# communication_module_20190916_bus-revise.net
KiCad netlist of a schematic drawn in EAGLE
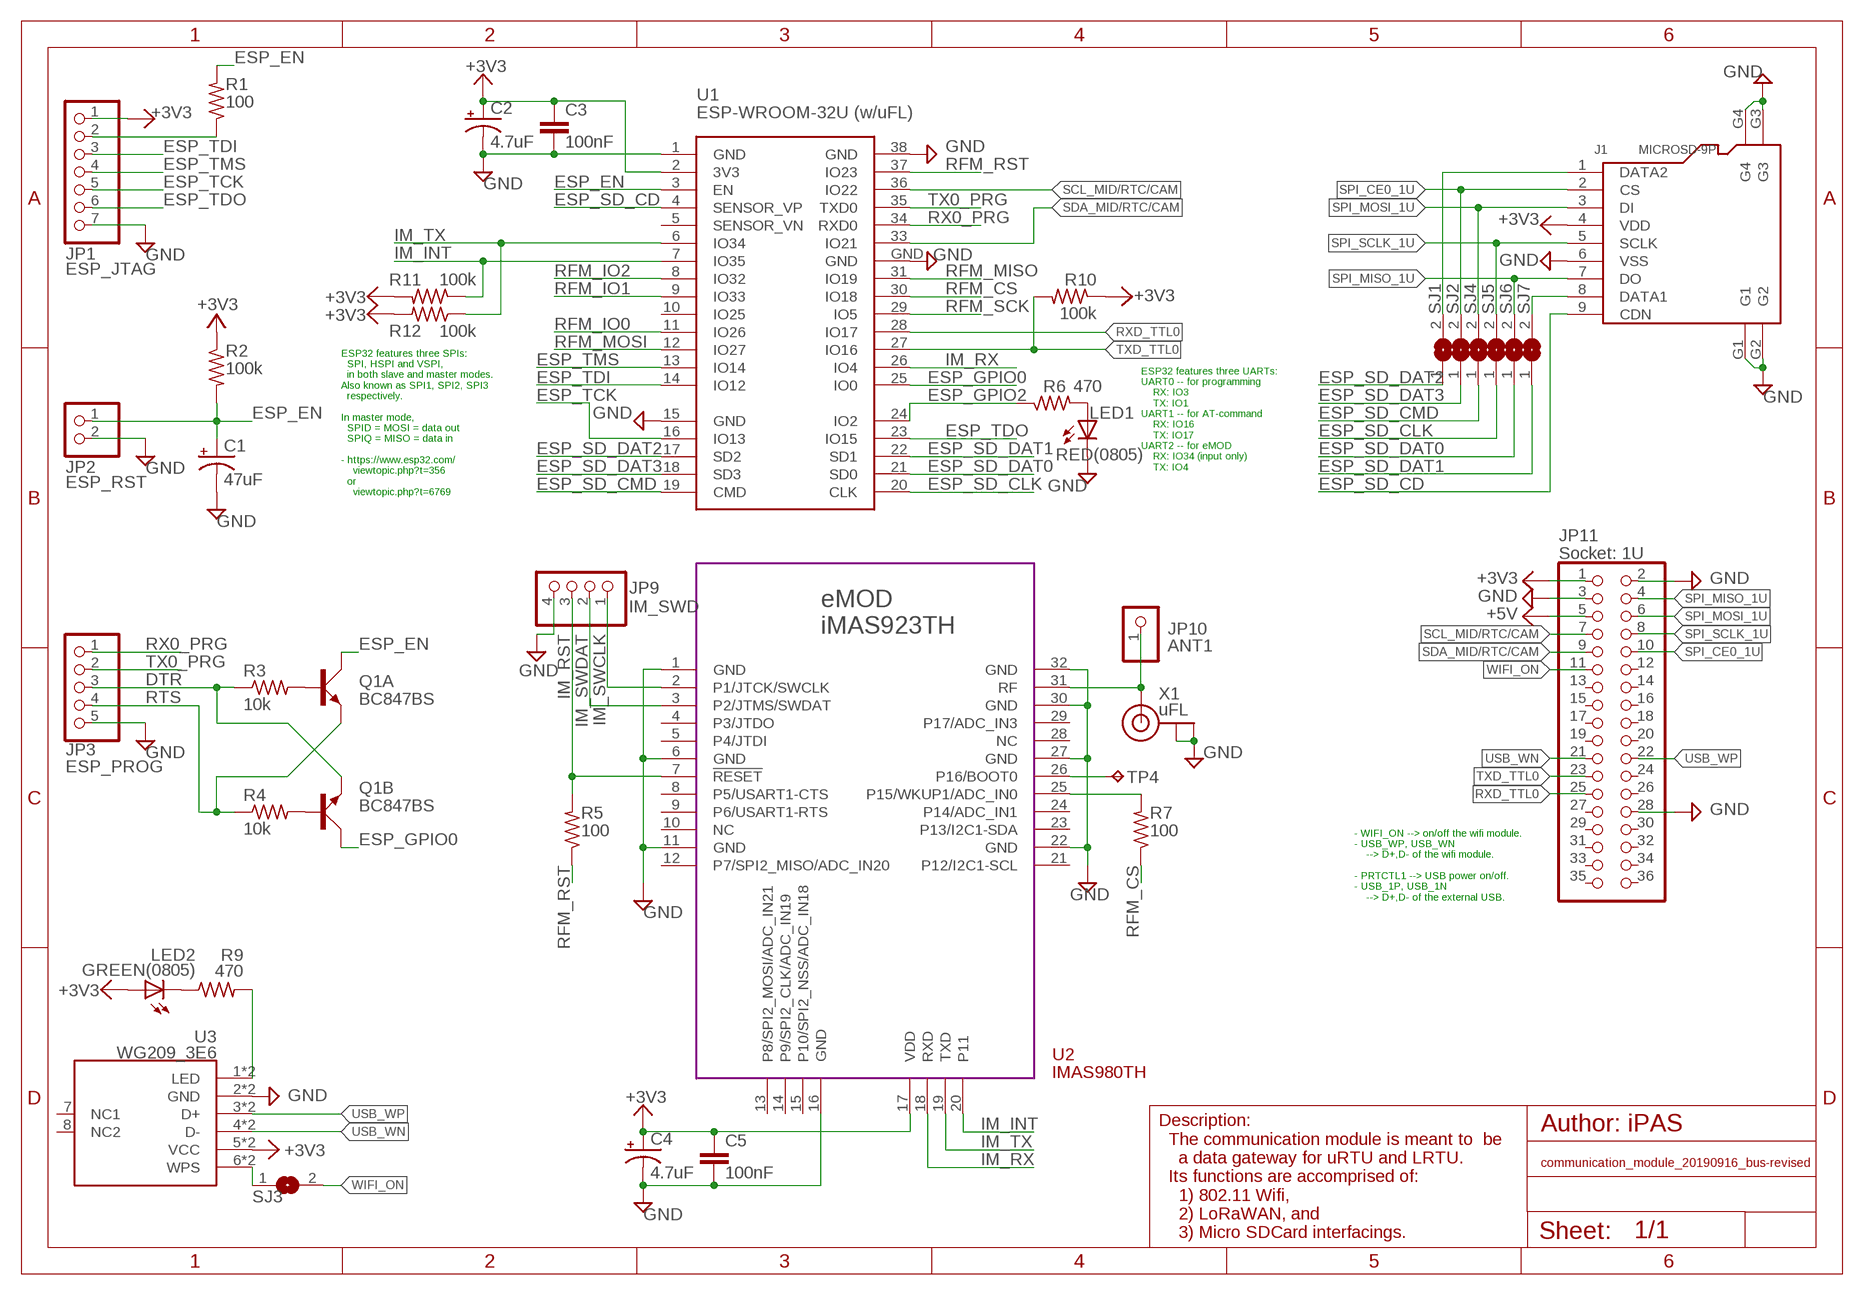
[diagram p0: schematic, sheet 1]

(export (version "E")
  (design (tool "Eeschema 10.0.6"))
  (components
    (comp (ref "C1")
      (value "47uF")
      (footprint "eagle-import:RCL_150CLZ-1014")
      (libsource (lib "eagle-import") (part "RCL_CPOL-US150CLZ-1014"))
    )
    (comp (ref "C2")
      (value "4.7uF")
      (footprint "eagle-import:RCL_150CLZ-1014")
      (libsource (lib "eagle-import") (part "RCL_CPOL-US150CLZ-1014"))
    )
    (comp (ref "C3")
      (value "100nF")
      (footprint "eagle-import:RCL_C1206")
      (libsource (lib "eagle-import") (part "RCL_C-EUC1206"))
    )
    (comp (ref "C4")
      (value "4.7uF")
      (footprint "eagle-import:RCL_150CLZ-1014")
      (libsource (lib "eagle-import") (part "RCL_CPOL-US150CLZ-1014"))
    )
    (comp (ref "C5")
      (value "100nF")
      (footprint "eagle-import:RCL_C1206")
      (libsource (lib "eagle-import") (part "RCL_C-EUC1206"))
    )
    (comp (ref "J1")
      (value "MICROSD-9P")
      (footprint "eagle-import:MICRO-SD9+4P-SMD-16.1X14.5X1.85MM")
      (libsource (lib "eagle-import") (part "MICRO-SD-CARD-HOLDER-9P"))
    )
    (comp (ref "JP1")
      (value "ESP_JTAG")
      (footprint "eagle-import:1X07")
      (libsource (lib "eagle-import") (part "PINHD-1X7"))
    )
    (comp (ref "JP2")
      (value "ESP_RST")
      (footprint "eagle-import:1X02")
      (libsource (lib "eagle-import") (part "PINHD-1X2"))
    )
    (comp (ref "JP3")
      (value "ESP_PROG")
      (footprint "eagle-import:1X05")
      (libsource (lib "eagle-import") (part "PINHD-1X5"))
    )
    (comp (ref "JP9")
      (value "IM_SWD")
      (footprint "eagle-import:1X04")
      (libsource (lib "eagle-import") (part "PINHD-1X4"))
    )
    (comp (ref "JP10")
      (value "ANT1")
      (footprint "eagle-import:1X01_ROUND")
      (libsource (lib "eagle-import") (part "HEADER-1X1ROUND"))
    )
    (comp (ref "JP11")
      (value "Socket: 1U")
      (footprint "eagle-import:2X18")
      (libsource (lib "eagle-import") (part "PINHD-2X18"))
    )
    (comp (ref "LED1")
      (value "RED(0805)")
      (footprint "eagle-import:CHIP-LED0805")
      (libsource (lib "eagle-import") (part "LEDCHIP-LED0805"))
    )
    (comp (ref "LED2")
      (value "GREEN(0805)")
      (footprint "eagle-import:CHIP-LED0805")
      (libsource (lib "eagle-import") (part "LEDCHIP-LED0805"))
    )
    (comp (ref "Q1")
      (value "BC847BS")
      (footprint "eagle-import:SOT363_PHILIPS")
      (libsource (lib "eagle-import") (part "BC847BS"))
    )
    (comp (ref "R1")
      (value "100")
      (footprint "eagle-import:RCL_M0805")
      (libsource (lib "eagle-import") (part "RCL_R-USM0805"))
    )
    (comp (ref "R2")
      (value "100k")
      (footprint "eagle-import:RCL_M0805")
      (libsource (lib "eagle-import") (part "RCL_R-USM0805"))
    )
    (comp (ref "R3")
      (value "10k")
      (footprint "eagle-import:RCL_M0805")
      (libsource (lib "eagle-import") (part "RCL_R-USM0805"))
    )
    (comp (ref "R4")
      (value "10k")
      (footprint "eagle-import:RCL_M0805")
      (libsource (lib "eagle-import") (part "RCL_R-USM0805"))
    )
    (comp (ref "R5")
      (value "100")
      (footprint "eagle-import:RCL_M0805")
      (libsource (lib "eagle-import") (part "RCL_R-USM0805"))
    )
    (comp (ref "R6")
      (value "470")
      (footprint "eagle-import:RCL_M0805")
      (libsource (lib "eagle-import") (part "RCL_R-USM0805"))
    )
    (comp (ref "R7")
      (value "100")
      (footprint "eagle-import:RCL_M0805")
      (libsource (lib "eagle-import") (part "RCL_R-USM0805"))
    )
    (comp (ref "R9")
      (value "470")
      (footprint "eagle-import:RCL_M0805")
      (libsource (lib "eagle-import") (part "RCL_R-USM0805"))
    )
    (comp (ref "R10")
      (value "100k")
      (footprint "eagle-import:RCL_M0805")
      (libsource (lib "eagle-import") (part "RCL_R-USM0805"))
    )
    (comp (ref "R11")
      (value "100k")
      (footprint "eagle-import:RCL_M0805")
      (libsource (lib "eagle-import") (part "RCL_R-USM0805"))
    )
    (comp (ref "R12")
      (value "100k")
      (footprint "eagle-import:RCL_M0805")
      (libsource (lib "eagle-import") (part "RCL_R-USM0805"))
    )
    (comp (ref "SJ1")
      (value "SOLDERJUMPERREFLOW")
      (footprint "eagle-import:SOLDERJUMPER_REFLOW")
      (libsource (lib "eagle-import") (part "SOLDERJUMPERREFLOW"))
    )
    (comp (ref "SJ2")
      (value "SOLDERJUMPERREFLOW")
      (footprint "eagle-import:SOLDERJUMPER_REFLOW")
      (libsource (lib "eagle-import") (part "SOLDERJUMPERREFLOW"))
    )
    (comp (ref "SJ3")
      (value "SOLDERJUMPERREFLOW")
      (footprint "eagle-import:SOLDERJUMPER_REFLOW")
      (libsource (lib "eagle-import") (part "SOLDERJUMPERREFLOW"))
    )
    (comp (ref "SJ4")
      (value "SOLDERJUMPERREFLOW")
      (footprint "eagle-import:SOLDERJUMPER_REFLOW")
      (libsource (lib "eagle-import") (part "SOLDERJUMPERREFLOW"))
    )
    (comp (ref "SJ5")
      (value "SOLDERJUMPERREFLOW")
      (footprint "eagle-import:SOLDERJUMPER_REFLOW")
      (libsource (lib "eagle-import") (part "SOLDERJUMPERREFLOW"))
    )
    (comp (ref "SJ6")
      (value "SOLDERJUMPERREFLOW")
      (footprint "eagle-import:SOLDERJUMPER_REFLOW")
      (libsource (lib "eagle-import") (part "SOLDERJUMPERREFLOW"))
    )
    (comp (ref "SJ7")
      (value "SOLDERJUMPERREFLOW")
      (footprint "eagle-import:SOLDERJUMPER_REFLOW")
      (libsource (lib "eagle-import") (part "SOLDERJUMPERREFLOW"))
    )
    (comp (ref "TP4")
      (value "TPB1,27")
      (footprint "eagle-import:B1,27")
      (libsource (lib "eagle-import") (part "TPB1,27"))
    )
    (comp (ref "U1")
      (value "ESP-WROOM-32U (w/uFL)")
      (footprint "eagle-import:ESP-WROOM-32")
      (libsource (lib "eagle-import") (part "ESP-WROOM-32"))
    )
    (comp (ref "U2")
      (value "IMAS980TH")
      (footprint "eagle-import:IMAS923TH")
      (libsource (lib "eagle-import") (part "IMAS980TH"))
    )
    (comp (ref "U3")
      (value "WG209_3E6")
      (footprint "eagle-import:WG209")
      (libsource (lib "eagle-import") (part "WG209"))
    )
    (comp (ref "X1")
      (value "uFL")
      (footprint "eagle-import:U.FL")
      (libsource (lib "eagle-import") (part "ANTENNA_U.FL"))
    )
  )
  (nets
    (net (code "1") (name "+3V3") (class "Default")
      (node (ref "C2") (pin "+") (pinfunction "+_+") (pintype "passive"))
      (node (ref "C3") (pin "1") (pinfunction "1_1") (pintype "passive"))
      (node (ref "C4") (pin "+") (pinfunction "+_+") (pintype "passive"))
      (node (ref "C5") (pin "1") (pinfunction "1_1") (pintype "passive"))
      (node (ref "J1") (pin "4") (pinfunction "VDD_4") (pintype "bidirectional"))
      (node (ref "JP1") (pin "1") (pinfunction "1_1") (pintype "passive"))
      (node (ref "JP11") (pin "1") (pinfunction "1_1") (pintype "passive"))
      (node (ref "LED2") (pin "A") (pinfunction "A_A") (pintype "passive"))
      (node (ref "R10") (pin "1") (pinfunction "1_1") (pintype "passive"))
      (node (ref "R11") (pin "2") (pinfunction "2_2") (pintype "passive"))
      (node (ref "R12") (pin "2") (pinfunction "2_2") (pintype "passive"))
      (node (ref "R2") (pin "1") (pinfunction "1_1") (pintype "passive"))
      (node (ref "U1") (pin "2") (pinfunction "3V3_2") (pintype "power_in"))
      (node (ref "U2") (pin "17") (pinfunction "VDD_17") (pintype "power_in"))
      (node (ref "U3") (pin "5") (pinfunction "VCC_5") (pintype "power_in"))
      (node (ref "U3") (pin "5P") (pinfunction "VCC_5P") (pintype "power_in"))
    )
    (net (code "2") (name "+5V") (class "Default")
      (node (ref "JP11") (pin "5") (pinfunction "5_5") (pintype "passive"))
    )
    (net (code "3") (name "/DTR") (class "Default")
      (node (ref "JP3") (pin "3") (pinfunction "3_3") (pintype "passive"))
      (node (ref "Q1") (pin "4") (pinfunction "E_4") (pintype "passive"))
      (node (ref "R3") (pin "1") (pinfunction "1_1") (pintype "passive"))
    )
    (net (code "4") (name "/ESP_EN") (class "Default")
      (node (ref "C1") (pin "+") (pinfunction "+_+") (pintype "passive"))
      (node (ref "JP2") (pin "1") (pinfunction "1_1") (pintype "passive"))
      (node (ref "Q1") (pin "6") (pinfunction "C_6") (pintype "passive"))
      (node (ref "R1") (pin "2") (pinfunction "2_2") (pintype "passive"))
      (node (ref "R2") (pin "2") (pinfunction "2_2") (pintype "passive"))
      (node (ref "U1") (pin "3") (pinfunction "EN_3") (pintype "input"))
    )
    (net (code "5") (name "/ESP_GPIO0") (class "Default")
      (node (ref "Q1") (pin "3") (pinfunction "C_3") (pintype "passive"))
      (node (ref "U1") (pin "25") (pinfunction "IO0_25") (pintype "bidirectional"))
    )
    (net (code "6") (name "/ESP_GPIO2") (class "Default")
      (node (ref "R6") (pin "1") (pinfunction "1_1") (pintype "passive"))
      (node (ref "U1") (pin "24") (pinfunction "IO2_24") (pintype "bidirectional"))
    )
    (net (code "7") (name "/ESP_SD_CD") (class "Default")
      (node (ref "J1") (pin "9") (pinfunction "CDN_9") (pintype "bidirectional"))
      (node (ref "U1") (pin "4") (pinfunction "SENSOR_VP_4") (pintype "bidirectional"))
    )
    (net (code "8") (name "/ESP_SD_CLK") (class "Default")
      (node (ref "SJ5") (pin "1") (pinfunction "1_1") (pintype "passive"))
      (node (ref "U1") (pin "20") (pinfunction "CLK_20") (pintype "bidirectional"))
    )
    (net (code "9") (name "/ESP_SD_CMD") (class "Default")
      (node (ref "SJ4") (pin "1") (pinfunction "1_1") (pintype "passive"))
      (node (ref "U1") (pin "19") (pinfunction "CMD_19") (pintype "bidirectional"))
    )
    (net (code "10") (name "/ESP_SD_DAT0") (class "Default")
      (node (ref "SJ6") (pin "1") (pinfunction "1_1") (pintype "passive"))
      (node (ref "U1") (pin "21") (pinfunction "SD0_21") (pintype "bidirectional"))
    )
    (net (code "11") (name "/ESP_SD_DAT1") (class "Default")
      (node (ref "SJ7") (pin "1") (pinfunction "1_1") (pintype "passive"))
      (node (ref "U1") (pin "22") (pinfunction "SD1_22") (pintype "bidirectional"))
    )
    (net (code "12") (name "/ESP_SD_DAT2") (class "Default")
      (node (ref "SJ1") (pin "1") (pinfunction "1_1") (pintype "passive"))
      (node (ref "U1") (pin "17") (pinfunction "SD2_17") (pintype "bidirectional"))
    )
    (net (code "13") (name "/ESP_SD_DAT3") (class "Default")
      (node (ref "SJ2") (pin "1") (pinfunction "1_1") (pintype "passive"))
      (node (ref "U1") (pin "18") (pinfunction "SD3_18") (pintype "bidirectional"))
    )
    (net (code "14") (name "/ESP_TCK") (class "Default")
      (node (ref "JP1") (pin "5") (pinfunction "5_5") (pintype "passive"))
      (node (ref "U1") (pin "16") (pinfunction "IO13_16") (pintype "bidirectional"))
    )
    (net (code "15") (name "/ESP_TDI") (class "Default")
      (node (ref "JP1") (pin "3") (pinfunction "3_3") (pintype "passive"))
      (node (ref "U1") (pin "14") (pinfunction "IO12_14") (pintype "bidirectional"))
    )
    (net (code "16") (name "/ESP_TDO") (class "Default")
      (node (ref "JP1") (pin "6") (pinfunction "6_6") (pintype "passive"))
      (node (ref "U1") (pin "23") (pinfunction "IO15_23") (pintype "bidirectional"))
    )
    (net (code "17") (name "/ESP_TMS") (class "Default")
      (node (ref "JP1") (pin "4") (pinfunction "4_4") (pintype "passive"))
      (node (ref "U1") (pin "13") (pinfunction "IO14_13") (pintype "bidirectional"))
    )
    (net (code "18") (name "/IM_INT") (class "Default")
      (node (ref "R11") (pin "1") (pinfunction "1_1") (pintype "passive"))
      (node (ref "U1") (pin "7") (pinfunction "IO35_7") (pintype "bidirectional"))
      (node (ref "U2") (pin "20") (pinfunction "P11_20") (pintype "bidirectional"))
    )
    (net (code "19") (name "/IM_RST") (class "Default")
      (node (ref "JP9") (pin "3") (pinfunction "3_3") (pintype "passive"))
      (node (ref "R5") (pin "2") (pinfunction "2_2") (pintype "passive"))
      (node (ref "U2") (pin "7") (pinfunction "~{RESET}_7") (pintype "passive"))
    )
    (net (code "20") (name "/IM_RX") (class "Default")
      (node (ref "U1") (pin "26") (pinfunction "IO4_26") (pintype "bidirectional"))
      (node (ref "U2") (pin "18") (pinfunction "RXD_18") (pintype "bidirectional"))
    )
    (net (code "21") (name "/IM_SWCLK") (class "Default")
      (node (ref "JP9") (pin "1") (pinfunction "1_1") (pintype "passive"))
      (node (ref "U2") (pin "2") (pinfunction "P1/JTCK/SWCLK_2") (pintype "bidirectional"))
    )
    (net (code "22") (name "/IM_SWDAT") (class "Default")
      (node (ref "JP9") (pin "2") (pinfunction "2_2") (pintype "passive"))
      (node (ref "U2") (pin "3") (pinfunction "P2/JTMS/SWDAT_3") (pintype "bidirectional"))
    )
    (net (code "23") (name "/IM_TX") (class "Default")
      (node (ref "R12") (pin "1") (pinfunction "1_1") (pintype "passive"))
      (node (ref "U1") (pin "6") (pinfunction "IO34_6") (pintype "bidirectional"))
      (node (ref "U2") (pin "19") (pinfunction "TXD_19") (pintype "bidirectional"))
    )
    (net (code "24") (name "/RFM_CS") (class "Default")
      (node (ref "R7") (pin "1") (pinfunction "1_1") (pintype "passive"))
      (node (ref "U1") (pin "30") (pinfunction "IO18_30") (pintype "bidirectional"))
    )
    (net (code "25") (name "/RFM_IO0") (class "Default")
      (node (ref "U1") (pin "11") (pinfunction "IO26_11") (pintype "bidirectional"))
    )
    (net (code "26") (name "/RFM_IO1") (class "Default")
      (node (ref "U1") (pin "9") (pinfunction "IO33_9") (pintype "bidirectional"))
    )
    (net (code "27") (name "/RFM_IO2") (class "Default")
      (node (ref "U1") (pin "8") (pinfunction "IO32_8") (pintype "bidirectional"))
    )
    (net (code "28") (name "/RFM_MISO") (class "Default")
      (node (ref "U1") (pin "31") (pinfunction "IO19_31") (pintype "bidirectional"))
    )
    (net (code "29") (name "/RFM_MOSI") (class "Default")
      (node (ref "U1") (pin "12") (pinfunction "IO27_12") (pintype "bidirectional"))
    )
    (net (code "30") (name "/RFM_RST") (class "Default")
      (node (ref "R5") (pin "1") (pinfunction "1_1") (pintype "passive"))
      (node (ref "U1") (pin "37") (pinfunction "IO23_37") (pintype "bidirectional"))
    )
    (net (code "31") (name "/RFM_SCK") (class "Default")
      (node (ref "U1") (pin "29") (pinfunction "IO5_29") (pintype "bidirectional"))
    )
    (net (code "32") (name "/RTS") (class "Default")
      (node (ref "JP3") (pin "4") (pinfunction "4_4") (pintype "passive"))
      (node (ref "Q1") (pin "1") (pinfunction "E_1") (pintype "passive"))
      (node (ref "R4") (pin "1") (pinfunction "1_1") (pintype "passive"))
    )
    (net (code "33") (name "/RX0_PRG") (class "Default")
      (node (ref "JP3") (pin "1") (pinfunction "1_1") (pintype "passive"))
      (node (ref "U1") (pin "34") (pinfunction "RXD0_34") (pintype "bidirectional"))
    )
    (net (code "34") (name "/TX0_PRG") (class "Default")
      (node (ref "JP3") (pin "2") (pinfunction "2_2") (pintype "passive"))
      (node (ref "U1") (pin "35") (pinfunction "TXD0_35") (pintype "bidirectional"))
    )
    (net (code "35") (name "GND") (class "Default")
      (node (ref "C1") (pin "-") (pinfunction "-_-") (pintype "passive"))
      (node (ref "C2") (pin "-") (pinfunction "-_-") (pintype "passive"))
      (node (ref "C3") (pin "2") (pinfunction "2_2") (pintype "passive"))
      (node (ref "C4") (pin "-") (pinfunction "-_-") (pintype "passive"))
      (node (ref "C5") (pin "2") (pinfunction "2_2") (pintype "passive"))
      (node (ref "J1") (pin "6") (pinfunction "VSS_6") (pintype "bidirectional"))
      (node (ref "J1") (pin "G1") (pinfunction "G1_G1") (pintype "bidirectional"))
      (node (ref "J1") (pin "G2") (pinfunction "G2_G2") (pintype "bidirectional"))
      (node (ref "J1") (pin "G3") (pinfunction "G3_G3") (pintype "bidirectional"))
      (node (ref "J1") (pin "G4") (pinfunction "G4_G4") (pintype "bidirectional"))
      (node (ref "JP1") (pin "7") (pinfunction "7_7") (pintype "passive"))
      (node (ref "JP11") (pin "2") (pinfunction "2_2") (pintype "passive"))
      (node (ref "JP11") (pin "28") (pinfunction "28_28") (pintype "passive"))
      (node (ref "JP11") (pin "3") (pinfunction "3_3") (pintype "passive"))
      (node (ref "JP2") (pin "2") (pinfunction "2_2") (pintype "passive"))
      (node (ref "JP3") (pin "5") (pinfunction "5_5") (pintype "passive"))
      (node (ref "JP9") (pin "4") (pinfunction "4_4") (pintype "passive"))
      (node (ref "LED1") (pin "C") (pinfunction "C_C") (pintype "passive"))
      (node (ref "U1") (pin "1") (pinfunction "GND_1") (pintype "power_in"))
      (node (ref "U1") (pin "15") (pinfunction "GND_15") (pintype "power_in"))
      (node (ref "U1") (pin "38") (pinfunction "GND_38") (pintype "power_in"))
      (node (ref "U1") (pin "GND") (pinfunction "GND_GND") (pintype "power_in"))
      (node (ref "U2") (pin "1") (pinfunction "GND_1") (pintype "power_in"))
      (node (ref "U2") (pin "11") (pinfunction "GND_11") (pintype "power_in"))
      (node (ref "U2") (pin "16") (pinfunction "GND_16") (pintype "power_in"))
      (node (ref "U2") (pin "22") (pinfunction "GND_22") (pintype "power_in"))
      (node (ref "U2") (pin "27") (pinfunction "GND_27") (pintype "power_in"))
      (node (ref "U2") (pin "30") (pinfunction "GND_30") (pintype "power_in"))
      (node (ref "U2") (pin "32") (pinfunction "GND_32") (pintype "power_in"))
      (node (ref "U2") (pin "6") (pinfunction "GND_6") (pintype "power_in"))
      (node (ref "U3") (pin "2") (pinfunction "GND_2") (pintype "power_in"))
      (node (ref "U3") (pin "2P") (pinfunction "GND_2P") (pintype "power_in"))
      (node (ref "X1") (pin "1") (pinfunction "GND_1") (pintype "passive"))
      (node (ref "X1") (pin "2") (pinfunction "GND_2") (pintype "passive"))
    )
    (net (code "36") (name "Net-(J1-DATA1)") (class "Default")
      (node (ref "J1") (pin "8") (pinfunction "DATA1_8") (pintype "bidirectional"))
      (node (ref "SJ7") (pin "2") (pinfunction "2_2") (pintype "passive"))
    )
    (net (code "37") (name "Net-(J1-DATA2)") (class "Default")
      (node (ref "J1") (pin "1") (pinfunction "DATA2_1") (pintype "bidirectional"))
      (node (ref "SJ1") (pin "2") (pinfunction "2_2") (pintype "passive"))
    )
    (net (code "38") (name "Net-(JP1-Pad2)") (class "Default")
      (node (ref "JP1") (pin "2") (pinfunction "2_2") (pintype "passive"))
      (node (ref "R1") (pin "1") (pinfunction "1_1") (pintype "passive"))
    )
    (net (code "39") (name "Net-(LED1-PadA)") (class "Default")
      (node (ref "LED1") (pin "A") (pinfunction "A_A") (pintype "passive"))
      (node (ref "R6") (pin "2") (pinfunction "2_2") (pintype "passive"))
    )
    (net (code "40") (name "Net-(LED2-PadC)") (class "Default")
      (node (ref "LED2") (pin "C") (pinfunction "C_C") (pintype "passive"))
      (node (ref "R9") (pin "1") (pinfunction "1_1") (pintype "passive"))
    )
    (net (code "41") (name "Net-(Q1A-B)") (class "Default")
      (node (ref "Q1") (pin "2") (pinfunction "B_2") (pintype "passive"))
      (node (ref "R3") (pin "2") (pinfunction "2_2") (pintype "passive"))
    )
    (net (code "42") (name "Net-(Q1B-B)") (class "Default")
      (node (ref "Q1") (pin "5") (pinfunction "B_5") (pintype "passive"))
      (node (ref "R4") (pin "2") (pinfunction "2_2") (pintype "passive"))
    )
    (net (code "43") (name "Net-(R9-Pad2)") (class "Default")
      (node (ref "R9") (pin "2") (pinfunction "2_2") (pintype "passive"))
      (node (ref "U3") (pin "1") (pinfunction "LED_1") (pintype "bidirectional"))
      (node (ref "U3") (pin "1P") (pinfunction "LED_1P") (pintype "bidirectional"))
    )
    (net (code "44") (name "Net-(SJ3-Pad1)") (class "Default")
      (node (ref "SJ3") (pin "1") (pinfunction "1_1") (pintype "passive"))
      (node (ref "U3") (pin "6") (pinfunction "WPS_6") (pintype "bidirectional"))
      (node (ref "U3") (pin "6P") (pinfunction "WPS_6P") (pintype "bidirectional"))
    )
    (net (code "45") (name "Net-(U2-P15{slash}WKUP1{slash}ADC_IN0)") (class "Default")
      (node (ref "R7") (pin "2") (pinfunction "2_2") (pintype "passive"))
      (node (ref "U2") (pin "25") (pinfunction "P15/WKUP1/ADC_IN0_25") (pintype "bidirectional"))
    )
    (net (code "46") (name "Net-(U2-P16{slash}BOOT0)") (class "Default")
      (node (ref "TP4") (pin "TP") (pinfunction "TP_TP") (pintype "input"))
      (node (ref "U2") (pin "26") (pinfunction "P16/BOOT0_26") (pintype "passive"))
    )
    (net (code "47") (name "Net-(U2-RF)") (class "Default")
      (node (ref "JP10") (pin "1") (pinfunction "1_1") (pintype "passive"))
      (node (ref "U2") (pin "31") (pinfunction "RF_31") (pintype "bidirectional"))
      (node (ref "X1") (pin "3") (pinfunction "SIGNAL_3") (pintype "passive"))
    )
    (net (code "48") (name "RXD_TTL0") (class "Default")
      (node (ref "JP11") (pin "25") (pinfunction "25_25") (pintype "passive"))
      (node (ref "U1") (pin "28") (pinfunction "IO17_28") (pintype "bidirectional"))
    )
    (net (code "49") (name "SCL_MID{slash}RTC{slash}CAM") (class "Default")
      (node (ref "JP11") (pin "7") (pinfunction "7_7") (pintype "passive"))
      (node (ref "U1") (pin "36") (pinfunction "IO22_36") (pintype "bidirectional"))
    )
    (net (code "50") (name "SDA_MID{slash}RTC{slash}CAM") (class "Default")
      (node (ref "JP11") (pin "9") (pinfunction "9_9") (pintype "passive"))
      (node (ref "U1") (pin "33") (pinfunction "IO21_33") (pintype "bidirectional"))
    )
    (net (code "51") (name "SPI_CE0_1U") (class "Default")
      (node (ref "J1") (pin "2") (pinfunction "CS_2") (pintype "bidirectional"))
      (node (ref "JP11") (pin "10") (pinfunction "10_10") (pintype "passive"))
      (node (ref "SJ2") (pin "2") (pinfunction "2_2") (pintype "passive"))
    )
    (net (code "52") (name "SPI_MISO_1U") (class "Default")
      (node (ref "J1") (pin "7") (pinfunction "DO_7") (pintype "bidirectional"))
      (node (ref "JP11") (pin "4") (pinfunction "4_4") (pintype "passive"))
      (node (ref "SJ6") (pin "2") (pinfunction "2_2") (pintype "passive"))
    )
    (net (code "53") (name "SPI_MOSI_1U") (class "Default")
      (node (ref "J1") (pin "3") (pinfunction "DI_3") (pintype "bidirectional"))
      (node (ref "JP11") (pin "6") (pinfunction "6_6") (pintype "passive"))
      (node (ref "SJ4") (pin "2") (pinfunction "2_2") (pintype "passive"))
    )
    (net (code "54") (name "SPI_SCLK_1U") (class "Default")
      (node (ref "J1") (pin "5") (pinfunction "SCLK_5") (pintype "bidirectional"))
      (node (ref "JP11") (pin "8") (pinfunction "8_8") (pintype "passive"))
      (node (ref "SJ5") (pin "2") (pinfunction "2_2") (pintype "passive"))
    )
    (net (code "55") (name "TXD_TTL0") (class "Default")
      (node (ref "JP11") (pin "23") (pinfunction "23_23") (pintype "passive"))
      (node (ref "R10") (pin "2") (pinfunction "2_2") (pintype "passive"))
      (node (ref "U1") (pin "27") (pinfunction "IO16_27") (pintype "bidirectional"))
    )
    (net (code "56") (name "USB_WN") (class "Default")
      (node (ref "JP11") (pin "21") (pinfunction "21_21") (pintype "passive"))
      (node (ref "U3") (pin "4") (pinfunction "D-_4") (pintype "bidirectional"))
      (node (ref "U3") (pin "4P") (pinfunction "D-_4P") (pintype "bidirectional"))
    )
    (net (code "57") (name "USB_WP") (class "Default")
      (node (ref "JP11") (pin "22") (pinfunction "22_22") (pintype "passive"))
      (node (ref "U3") (pin "3") (pinfunction "D+_3") (pintype "bidirectional"))
      (node (ref "U3") (pin "3P") (pinfunction "D+_3P") (pintype "bidirectional"))
    )
    (net (code "58") (name "WIFI_ON") (class "Default")
      (node (ref "JP11") (pin "11") (pinfunction "11_11") (pintype "passive"))
      (node (ref "SJ3") (pin "2") (pinfunction "2_2") (pintype "passive"))
    )
    (net (code "59") (name "unconnected-(JP11-Pad12)") (class "Default")
      (node (ref "JP11") (pin "12") (pinfunction "12_12") (pintype "passive"))
    )
    (net (code "60") (name "unconnected-(JP11-Pad13)") (class "Default")
      (node (ref "JP11") (pin "13") (pinfunction "13_13") (pintype "passive"))
    )
    (net (code "61") (name "unconnected-(JP11-Pad14)") (class "Default")
      (node (ref "JP11") (pin "14") (pinfunction "14_14") (pintype "passive"))
    )
    (net (code "62") (name "unconnected-(JP11-Pad15)") (class "Default")
      (node (ref "JP11") (pin "15") (pinfunction "15_15") (pintype "passive"))
    )
    (net (code "63") (name "unconnected-(JP11-Pad16)") (class "Default")
      (node (ref "JP11") (pin "16") (pinfunction "16_16") (pintype "passive"))
    )
    (net (code "64") (name "unconnected-(JP11-Pad17)") (class "Default")
      (node (ref "JP11") (pin "17") (pinfunction "17_17") (pintype "passive"))
    )
    (net (code "65") (name "unconnected-(JP11-Pad18)") (class "Default")
      (node (ref "JP11") (pin "18") (pinfunction "18_18") (pintype "passive"))
    )
    (net (code "66") (name "unconnected-(JP11-Pad19)") (class "Default")
      (node (ref "JP11") (pin "19") (pinfunction "19_19") (pintype "passive"))
    )
    (net (code "67") (name "unconnected-(JP11-Pad20)") (class "Default")
      (node (ref "JP11") (pin "20") (pinfunction "20_20") (pintype "passive"))
    )
    (net (code "68") (name "unconnected-(JP11-Pad24)") (class "Default")
      (node (ref "JP11") (pin "24") (pinfunction "24_24") (pintype "passive"))
    )
    (net (code "69") (name "unconnected-(JP11-Pad26)") (class "Default")
      (node (ref "JP11") (pin "26") (pinfunction "26_26") (pintype "passive"))
    )
    (net (code "70") (name "unconnected-(JP11-Pad27)") (class "Default")
      (node (ref "JP11") (pin "27") (pinfunction "27_27") (pintype "passive"))
    )
    (net (code "71") (name "unconnected-(JP11-Pad29)") (class "Default")
      (node (ref "JP11") (pin "29") (pinfunction "29_29") (pintype "passive"))
    )
    (net (code "72") (name "unconnected-(JP11-Pad30)") (class "Default")
      (node (ref "JP11") (pin "30") (pinfunction "30_30") (pintype "passive"))
    )
    (net (code "73") (name "unconnected-(JP11-Pad31)") (class "Default")
      (node (ref "JP11") (pin "31") (pinfunction "31_31") (pintype "passive"))
    )
    (net (code "74") (name "unconnected-(JP11-Pad32)") (class "Default")
      (node (ref "JP11") (pin "32") (pinfunction "32_32") (pintype "passive"))
    )
    (net (code "75") (name "unconnected-(JP11-Pad33)") (class "Default")
      (node (ref "JP11") (pin "33") (pinfunction "33_33") (pintype "passive"))
    )
    (net (code "76") (name "unconnected-(JP11-Pad34)") (class "Default")
      (node (ref "JP11") (pin "34") (pinfunction "34_34") (pintype "passive"))
    )
    (net (code "77") (name "unconnected-(JP11-Pad35)") (class "Default")
      (node (ref "JP11") (pin "35") (pinfunction "35_35") (pintype "passive"))
    )
    (net (code "78") (name "unconnected-(JP11-Pad36)") (class "Default")
      (node (ref "JP11") (pin "36") (pinfunction "36_36") (pintype "passive"))
    )
    (net (code "79") (name "unconnected-(U1-IO25-Pad10)") (class "Default")
      (node (ref "U1") (pin "10") (pinfunction "IO25_10") (pintype "bidirectional"))
    )
    (net (code "80") (name "unconnected-(U1-SENSOR_VN-Pad5)") (class "Default")
      (node (ref "U1") (pin "5") (pinfunction "SENSOR_VN_5") (pintype "bidirectional"))
    )
    (net (code "81") (name "unconnected-(U2-NC-Pad10)") (class "Default")
      (node (ref "U2") (pin "10") (pinfunction "NC_10") (pintype "no_connect"))
    )
    (net (code "82") (name "unconnected-(U2-NC-Pad28)") (class "Default")
      (node (ref "U2") (pin "28") (pinfunction "NC_28") (pintype "no_connect"))
    )
    (net (code "83") (name "unconnected-(U2-P3{slash}JTDO-Pad4)") (class "Default")
      (node (ref "U2") (pin "4") (pinfunction "P3/JTDO_4") (pintype "bidirectional"))
    )
    (net (code "84") (name "unconnected-(U2-P4{slash}JTDI-Pad5)") (class "Default")
      (node (ref "U2") (pin "5") (pinfunction "P4/JTDI_5") (pintype "bidirectional"))
    )
    (net (code "85") (name "unconnected-(U2-P5{slash}USART1-CTS-Pad8)") (class "Default")
      (node (ref "U2") (pin "8") (pinfunction "P5/USART1-CTS_8") (pintype "bidirectional"))
    )
    (net (code "86") (name "unconnected-(U2-P6{slash}USART1-RTS-Pad9)") (class "Default")
      (node (ref "U2") (pin "9") (pinfunction "P6/USART1-RTS_9") (pintype "bidirectional"))
    )
    (net (code "87") (name "unconnected-(U2-P7{slash}SPI2_MISO{slash}ADC_IN20-Pad12)") (class "Default")
      (node (ref "U2") (pin "12") (pinfunction "P7/SPI2_MISO/ADC_IN20_12") (pintype "bidirectional"))
    )
    (net (code "88") (name "unconnected-(U2-P8{slash}SPI2_MOSI{slash}ADC_IN21-Pad13)") (class "Default")
      (node (ref "U2") (pin "13") (pinfunction "P8/SPI2_MOSI/ADC_IN21_13") (pintype "bidirectional"))
    )
    (net (code "89") (name "unconnected-(U2-P9{slash}SPI2_CLK{slash}ADC_IN19-Pad14)") (class "Default")
      (node (ref "U2") (pin "14") (pinfunction "P9/SPI2_CLK/ADC_IN19_14") (pintype "bidirectional"))
    )
    (net (code "90") (name "unconnected-(U2-P10{slash}SPI2_NSS{slash}ADC_IN18-Pad15)") (class "Default")
      (node (ref "U2") (pin "15") (pinfunction "P10/SPI2_NSS/ADC_IN18_15") (pintype "bidirectional"))
    )
    (net (code "91") (name "unconnected-(U2-P12{slash}I2C1-SCL-Pad21)") (class "Default")
      (node (ref "U2") (pin "21") (pinfunction "P12/I2C1-SCL_21") (pintype "bidirectional"))
    )
    (net (code "92") (name "unconnected-(U2-P13{slash}I2C1-SDA-Pad23)") (class "Default")
      (node (ref "U2") (pin "23") (pinfunction "P13/I2C1-SDA_23") (pintype "bidirectional"))
    )
    (net (code "93") (name "unconnected-(U2-P14{slash}ADC_IN1-Pad24)") (class "Default")
      (node (ref "U2") (pin "24") (pinfunction "P14/ADC_IN1_24") (pintype "bidirectional"))
    )
    (net (code "94") (name "unconnected-(U2-P17{slash}ADC_IN3-Pad29)") (class "Default")
      (node (ref "U2") (pin "29") (pinfunction "P17/ADC_IN3_29") (pintype "bidirectional"))
    )
    (net (code "95") (name "unconnected-(U3-NC1-Pad7)") (class "Default")
      (node (ref "U3") (pin "7") (pinfunction "NC1_7") (pintype "no_connect"))
    )
    (net (code "96") (name "unconnected-(U3-NC2-Pad8)") (class "Default")
      (node (ref "U3") (pin "8") (pinfunction "NC2_8") (pintype "no_connect"))
    )
  )
)
